# printTumblerRev1.net
KiCad netlist of a schematic drawn in EAGLE
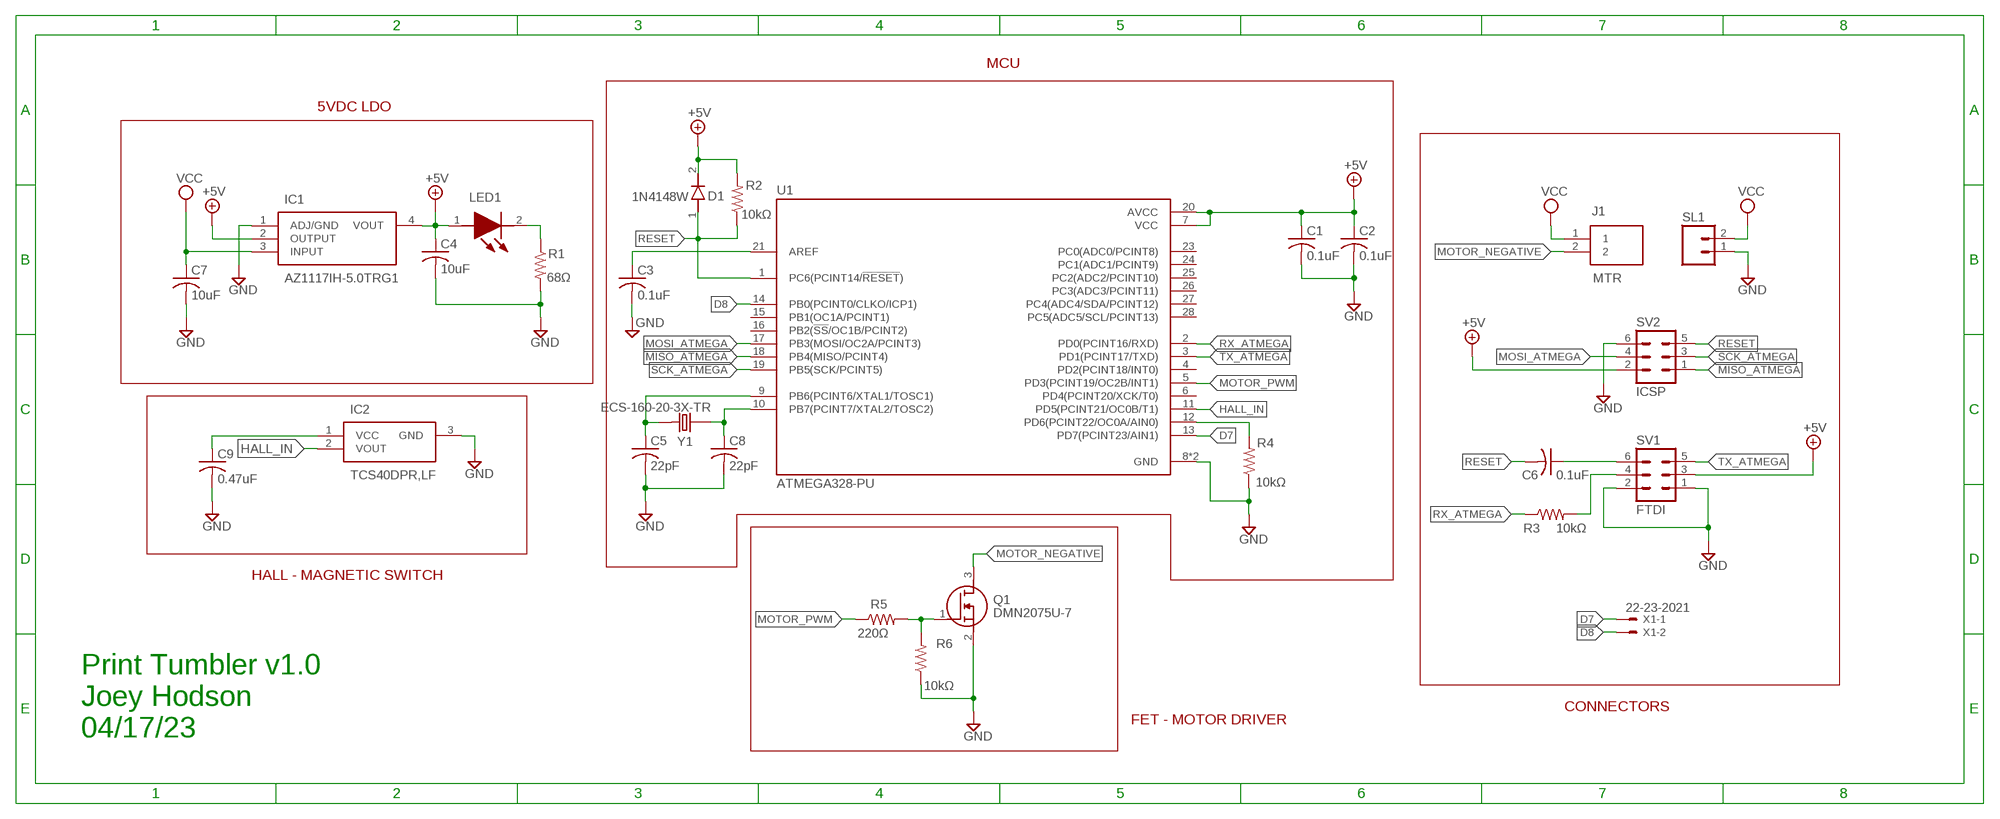
[diagram p0: schematic, sheet 1]

(export (version "E")
  (design (tool "Eeschema 10.0.6"))
  (components
    (comp (ref "C1")
      (value "0.1uF")
      (footprint "eagle-import:C0603")
      (libsource (lib "eagle-import") (part "C-USC0603"))
    )
    (comp (ref "C2")
      (value "0.1uF")
      (footprint "eagle-import:C0603")
      (libsource (lib "eagle-import") (part "C-USC0603"))
    )
    (comp (ref "C3")
      (value "0.1uF")
      (footprint "eagle-import:C0603")
      (libsource (lib "eagle-import") (part "C-USC0603"))
    )
    (comp (ref "C4")
      (value "10uF")
      (footprint "eagle-import:C0805")
      (libsource (lib "eagle-import") (part "C-USC0805"))
    )
    (comp (ref "C5")
      (value "22pF")
      (footprint "eagle-import:C0603")
      (libsource (lib "eagle-import") (part "C-USC0603"))
    )
    (comp (ref "C6")
      (value "0.1uF")
      (footprint "eagle-import:C0603")
      (libsource (lib "eagle-import") (part "C-USC0603"))
    )
    (comp (ref "C7")
      (value "10uF")
      (footprint "eagle-import:C0805")
      (libsource (lib "eagle-import") (part "C-USC0805"))
    )
    (comp (ref "C8")
      (value "22pF")
      (footprint "eagle-import:C0603")
      (libsource (lib "eagle-import") (part "C-USC0603"))
    )
    (comp (ref "C9")
      (value "0.47uF")
      (footprint "eagle-import:C0603")
      (libsource (lib "eagle-import") (part "C-USC0603"))
    )
    (comp (ref "D1")
      (value "1N4148W")
      (footprint "eagle-import:SOD523F")
      (fields (field (name "MF") "Diotec Semiconductor"))
      (libsource (lib "eagle-import") (part "1N4148W"))
    )
    (comp (ref "IC1")
      (value "AZ1117IH-5.0TRG1")
      (footprint "eagle-import:SOT230P700X170-4N")
      (fields (field (name "MOUSER_PART_NUMBER") "621-AZ1117IH-5.0TRG1"))
      (libsource (lib "eagle-import") (part "AZ1117IH-5.0TRG1"))
    )
    (comp (ref "IC2")
      (value "TCS40DPR,LF")
      (footprint "eagle-import:SOTFL95P240X88-3N")
      (fields (field (name "MOUSER_PART_NUMBER") "757-TCS40DPRLF"))
      (libsource (lib "eagle-import") (part "TCS40DPR,LF"))
    )
    (comp (ref "J1")
      (value "MTR")
      (footprint "eagle-import:SHDR2W90P0X381_1X2_802X740X850")
      (fields
        (field (name "MANUFACTURER_PART_NUMBER") "691214310002")
        (field (name "MOUSER_PART_NUMBER") "710-691214310002")
      )
      (libsource (lib "eagle-import") (part "691214310002"))
    )
    (comp (ref "LED1")
      (value "SML-LX0603IW-TR")
      (footprint "eagle-import:SMLLX0603IWTR")
      (fields (field (name "MOUSER_PART_NUMBER") "696-SML-LX0603IW"))
      (libsource (lib "eagle-import") (part "SML-LX0603IW-TR"))
    )
    (comp (ref "Q1")
      (value "DMN2075U-7")
      (footprint "eagle-import:SOT96P240X100-3N")
      (fields (field (name "MOUSER_PART_NUMBER") "621-DMN2075U-7"))
      (libsource (lib "eagle-import") (part "DMN2075U-7"))
    )
    (comp (ref "R1")
      (value "68Ω")
      (footprint "eagle-import:R0603")
      (libsource (lib "eagle-import") (part "R-US_R0603"))
    )
    (comp (ref "R2")
      (value "10kΩ")
      (footprint "eagle-import:R0603")
      (libsource (lib "eagle-import") (part "R-US_R0603"))
    )
    (comp (ref "R3")
      (value "10kΩ")
      (footprint "eagle-import:R0603")
      (libsource (lib "eagle-import") (part "R-US_R0603"))
    )
    (comp (ref "R4")
      (value "10kΩ")
      (footprint "eagle-import:R0603")
      (libsource (lib "eagle-import") (part "R-US_R0603"))
    )
    (comp (ref "R5")
      (value "220Ω")
      (footprint "eagle-import:R0603")
      (libsource (lib "eagle-import") (part "R-US_R0603"))
    )
    (comp (ref "R6")
      (value "10kΩ")
      (footprint "eagle-import:R0603")
      (libsource (lib "eagle-import") (part "R-US_R0603"))
    )
    (comp (ref "SL1")
      (value "M02")
      (footprint "eagle-import:02P")
      (libsource (lib "eagle-import") (part "M02"))
    )
    (comp (ref "SV1")
      (value "FTDI")
      (footprint "eagle-import:MA03-2")
      (libsource (lib "eagle-import") (part "MA03-2"))
    )
    (comp (ref "SV2")
      (value "ICSP")
      (footprint "eagle-import:MA03-2")
      (libsource (lib "eagle-import") (part "MA03-2"))
    )
    (comp (ref "U1")
      (value "ATMEGA328-PU")
      (footprint "eagle-import:DIP787W46P254L3467H508Q28")
      (fields (field (name "MF") "Microchip Technology") (field (name "MP") "ATMEGA328PU"))
      (libsource (lib "eagle-import") (part "ATMEGA328-PU"))
    )
    (comp (ref "X1")
      (value "22-23-2021")
      (footprint "eagle-import:22-23-2021")
      (fields (field (name "MF") "MOLEX"))
      (libsource (lib "eagle-import") (part "22-23-2021"))
    )
    (comp (ref "Y1")
      (value "ECS-160-20-3X-TR")
      (footprint "eagle-import:XTAL_ECS-160-20-3X-TR")
      (fields (field (name "MF") "ECS Inc."))
      (libsource (lib "eagle-import") (part "ECS-160-20-3X-TR"))
    )
  )
  (nets
    (net (code "1") (name "+5V") (class "Default")
      (node (ref "C1") (pin "1") (pinfunction "1_1") (pintype "passive"))
      (node (ref "C2") (pin "1") (pinfunction "1_1") (pintype "passive"))
      (node (ref "C4") (pin "1") (pinfunction "1_1") (pintype "passive"))
      (node (ref "D1") (pin "2") (pinfunction "C1_2") (pintype "passive"))
      (node (ref "IC1") (pin "2") (pinfunction "OUTPUT_2") (pintype "bidirectional"))
      (node (ref "IC1") (pin "4") (pinfunction "VOUT_4") (pintype "bidirectional"))
      (node (ref "LED1") (pin "1") (pinfunction "A_1") (pintype "bidirectional"))
      (node (ref "R2") (pin "2") (pinfunction "2_2") (pintype "passive"))
      (node (ref "SV1") (pin "3") (pinfunction "3_3") (pintype "passive"))
      (node (ref "SV2") (pin "2") (pinfunction "2_2") (pintype "passive"))
      (node (ref "U1") (pin "20") (pinfunction "AVCC_20") (pintype "power_in"))
      (node (ref "U1") (pin "7") (pinfunction "VCC_7") (pintype "power_in"))
    )
    (net (code "2") (name "D7") (class "Default")
      (node (ref "U1") (pin "13") (pinfunction "PD7(PCINT23/AIN1)_13") (pintype "bidirectional"))
      (node (ref "X1") (pin "1") (pinfunction "S_1") (pintype "passive"))
    )
    (net (code "3") (name "D8") (class "Default")
      (node (ref "U1") (pin "14") (pinfunction "PB0(PCINT0/CLKO/ICP1)_14") (pintype "bidirectional"))
      (node (ref "X1") (pin "2") (pinfunction "S_2") (pintype "passive"))
    )
    (net (code "4") (name "GND") (class "Default")
      (node (ref "C1") (pin "2") (pinfunction "2_2") (pintype "passive"))
      (node (ref "C2") (pin "2") (pinfunction "2_2") (pintype "passive"))
      (node (ref "C3") (pin "2") (pinfunction "2_2") (pintype "passive"))
      (node (ref "C4") (pin "2") (pinfunction "2_2") (pintype "passive"))
      (node (ref "C5") (pin "2") (pinfunction "2_2") (pintype "passive"))
      (node (ref "C7") (pin "2") (pinfunction "2_2") (pintype "passive"))
      (node (ref "C8") (pin "2") (pinfunction "2_2") (pintype "passive"))
      (node (ref "C9") (pin "2") (pinfunction "2_2") (pintype "passive"))
      (node (ref "IC1") (pin "1") (pinfunction "ADJ/GND_1") (pintype "bidirectional"))
      (node (ref "IC2") (pin "3") (pinfunction "GND_3") (pintype "bidirectional"))
      (node (ref "Q1") (pin "2") (pinfunction "S_2") (pintype "bidirectional"))
      (node (ref "R1") (pin "2") (pinfunction "2_2") (pintype "passive"))
      (node (ref "R4") (pin "1") (pinfunction "1_1") (pintype "passive"))
      (node (ref "R6") (pin "1") (pinfunction "1_1") (pintype "passive"))
      (node (ref "SL1") (pin "1") (pinfunction "1_1") (pintype "passive"))
      (node (ref "SV1") (pin "1") (pinfunction "1_1") (pintype "passive"))
      (node (ref "SV1") (pin "2") (pinfunction "2_2") (pintype "passive"))
      (node (ref "SV2") (pin "6") (pinfunction "6_6") (pintype "passive"))
      (node (ref "U1") (pin "22") (pinfunction "GND_22") (pintype "power_in"))
      (node (ref "U1") (pin "8") (pinfunction "GND_8") (pintype "power_in"))
    )
    (net (code "5") (name "HALL_IN") (class "Default")
      (node (ref "IC2") (pin "2") (pinfunction "VOUT_2") (pintype "bidirectional"))
      (node (ref "U1") (pin "11") (pinfunction "PD5(PCINT21/OC0B/T1)_11") (pintype "bidirectional"))
    )
    (net (code "6") (name "MISO_ATMEGA") (class "Default")
      (node (ref "SV2") (pin "1") (pinfunction "1_1") (pintype "passive"))
      (node (ref "U1") (pin "18") (pinfunction "PB4(MISO/PCINT4)_18") (pintype "bidirectional"))
    )
    (net (code "7") (name "MOSI_ATMEGA") (class "Default")
      (node (ref "SV2") (pin "4") (pinfunction "4_4") (pintype "passive"))
      (node (ref "U1") (pin "17") (pinfunction "PB3(MOSI/OC2A/PCINT3)_17") (pintype "bidirectional"))
    )
    (net (code "8") (name "MOTOR_NEGATIVE") (class "Default")
      (node (ref "J1") (pin "2") (pinfunction "2_2") (pintype "bidirectional"))
      (node (ref "Q1") (pin "3") (pinfunction "D_3") (pintype "bidirectional"))
    )
    (net (code "9") (name "MOTOR_PWM") (class "Default")
      (node (ref "R5") (pin "1") (pinfunction "1_1") (pintype "passive"))
      (node (ref "U1") (pin "5") (pinfunction "PD3(PCINT19/OC2B/INT1)_5") (pintype "bidirectional"))
    )
    (net (code "10") (name "Net-(C6-Pad1)") (class "Default")
      (node (ref "C6") (pin "1") (pinfunction "1_1") (pintype "passive"))
      (node (ref "SV1") (pin "6") (pinfunction "6_6") (pintype "passive"))
    )
    (net (code "11") (name "Net-(IC2-VCC)") (class "Default")
      (node (ref "C9") (pin "1") (pinfunction "1_1") (pintype "passive"))
      (node (ref "IC2") (pin "1") (pinfunction "VCC_1") (pintype "bidirectional"))
    )
    (net (code "12") (name "Net-(LED1-K)") (class "Default")
      (node (ref "LED1") (pin "2") (pinfunction "K_2") (pintype "bidirectional"))
      (node (ref "R1") (pin "1") (pinfunction "1_1") (pintype "passive"))
    )
    (net (code "13") (name "Net-(Q1-G)") (class "Default")
      (node (ref "Q1") (pin "1") (pinfunction "G_1") (pintype "bidirectional"))
      (node (ref "R5") (pin "2") (pinfunction "2_2") (pintype "passive"))
      (node (ref "R6") (pin "2") (pinfunction "2_2") (pintype "passive"))
    )
    (net (code "14") (name "Net-(R3-Pad2)") (class "Default")
      (node (ref "R3") (pin "2") (pinfunction "2_2") (pintype "passive"))
      (node (ref "SV1") (pin "4") (pinfunction "4_4") (pintype "passive"))
    )
    (net (code "15") (name "Net-(U1-AREF)") (class "Default")
      (node (ref "C3") (pin "1") (pinfunction "1_1") (pintype "passive"))
      (node (ref "U1") (pin "21") (pinfunction "AREF_21") (pintype "input"))
    )
    (net (code "16") (name "Net-(U1-PB6(PCINT6{slash}XTAL1{slash}TOSC1))") (class "Default")
      (node (ref "C5") (pin "1") (pinfunction "1_1") (pintype "passive"))
      (node (ref "U1") (pin "9") (pinfunction "PB6(PCINT6/XTAL1/TOSC1)_9") (pintype "bidirectional"))
      (node (ref "Y1") (pin "2") (pinfunction "2_2") (pintype "passive"))
    )
    (net (code "17") (name "Net-(U1-PB7(PCINT7{slash}XTAL2{slash}TOSC2))") (class "Default")
      (node (ref "C8") (pin "1") (pinfunction "1_1") (pintype "passive"))
      (node (ref "U1") (pin "10") (pinfunction "PB7(PCINT7/XTAL2/TOSC2)_10") (pintype "bidirectional"))
      (node (ref "Y1") (pin "1") (pinfunction "1_1") (pintype "passive"))
    )
    (net (code "18") (name "Net-(U1-PD6(PCINT22{slash}OC0A{slash}AIN0))") (class "Default")
      (node (ref "R4") (pin "2") (pinfunction "2_2") (pintype "passive"))
      (node (ref "U1") (pin "12") (pinfunction "PD6(PCINT22/OC0A/AIN0)_12") (pintype "bidirectional"))
    )
    (net (code "19") (name "RESET") (class "Default")
      (node (ref "C6") (pin "2") (pinfunction "2_2") (pintype "passive"))
      (node (ref "D1") (pin "1") (pinfunction "A1_1") (pintype "passive"))
      (node (ref "R2") (pin "1") (pinfunction "1_1") (pintype "passive"))
      (node (ref "SV2") (pin "5") (pinfunction "5_5") (pintype "passive"))
      (node (ref "U1") (pin "1") (pinfunction "PC6(PCINT14/~{RESET})_1") (pintype "bidirectional"))
    )
    (net (code "20") (name "RX_ATMEGA") (class "Default")
      (node (ref "R3") (pin "1") (pinfunction "1_1") (pintype "passive"))
      (node (ref "U1") (pin "2") (pinfunction "PD0(PCINT16/RXD)_2") (pintype "bidirectional"))
    )
    (net (code "21") (name "SCK_ATMEGA") (class "Default")
      (node (ref "SV2") (pin "3") (pinfunction "3_3") (pintype "passive"))
      (node (ref "U1") (pin "19") (pinfunction "PB5(SCK/PCINT5)_19") (pintype "bidirectional"))
    )
    (net (code "22") (name "TX_ATMEGA") (class "Default")
      (node (ref "SV1") (pin "5") (pinfunction "5_5") (pintype "passive"))
      (node (ref "U1") (pin "3") (pinfunction "PD1(PCINT17/TXD)_3") (pintype "bidirectional"))
    )
    (net (code "23") (name "VCC") (class "Default")
      (node (ref "C7") (pin "1") (pinfunction "1_1") (pintype "passive"))
      (node (ref "IC1") (pin "3") (pinfunction "INPUT_3") (pintype "bidirectional"))
      (node (ref "J1") (pin "1") (pinfunction "1_1") (pintype "bidirectional"))
      (node (ref "SL1") (pin "2") (pinfunction "2_2") (pintype "passive"))
    )
    (net (code "24") (name "unconnected-(U1-PB1(OC1A{slash}PCINT1)-Pad15)") (class "Default")
      (node (ref "U1") (pin "15") (pinfunction "PB1(OC1A/PCINT1)_15") (pintype "bidirectional"))
    )
    (net (code "25") (name "unconnected-(U1-PB2(~{SS}{slash}OC1B{slash}PCINT2)-Pad16)") (class "Default")
      (node (ref "U1") (pin "16") (pinfunction "PB2(~{SS}/OC1B/PCINT2)_16") (pintype "bidirectional"))
    )
    (net (code "26") (name "unconnected-(U1-PC0(ADC0{slash}PCINT8)-Pad23)") (class "Default")
      (node (ref "U1") (pin "23") (pinfunction "PC0(ADC0/PCINT8)_23") (pintype "bidirectional"))
    )
    (net (code "27") (name "unconnected-(U1-PC1(ADC1{slash}PCINT9)-Pad24)") (class "Default")
      (node (ref "U1") (pin "24") (pinfunction "PC1(ADC1/PCINT9)_24") (pintype "bidirectional"))
    )
    (net (code "28") (name "unconnected-(U1-PC2(ADC2{slash}PCINT10)-Pad25)") (class "Default")
      (node (ref "U1") (pin "25") (pinfunction "PC2(ADC2/PCINT10)_25") (pintype "bidirectional"))
    )
    (net (code "29") (name "unconnected-(U1-PC3(ADC3{slash}PCINT11)-Pad26)") (class "Default")
      (node (ref "U1") (pin "26") (pinfunction "PC3(ADC3/PCINT11)_26") (pintype "bidirectional"))
    )
    (net (code "30") (name "unconnected-(U1-PC4(ADC4{slash}SDA{slash}PCINT12)-Pad27)") (class "Default")
      (node (ref "U1") (pin "27") (pinfunction "PC4(ADC4/SDA/PCINT12)_27") (pintype "bidirectional"))
    )
    (net (code "31") (name "unconnected-(U1-PC5(ADC5{slash}SCL{slash}PCINT13)-Pad28)") (class "Default")
      (node (ref "U1") (pin "28") (pinfunction "PC5(ADC5/SCL/PCINT13)_28") (pintype "bidirectional"))
    )
    (net (code "32") (name "unconnected-(U1-PD2(PCINT18{slash}INT0)-Pad4)") (class "Default")
      (node (ref "U1") (pin "4") (pinfunction "PD2(PCINT18/INT0)_4") (pintype "bidirectional"))
    )
    (net (code "33") (name "unconnected-(U1-PD4(PCINT20{slash}XCK{slash}T0)-Pad6)") (class "Default")
      (node (ref "U1") (pin "6") (pinfunction "PD4(PCINT20/XCK/T0)_6") (pintype "bidirectional"))
    )
  )
)
